# Axel.net
KiCad netlist of a schematic drawn in Altium Designer
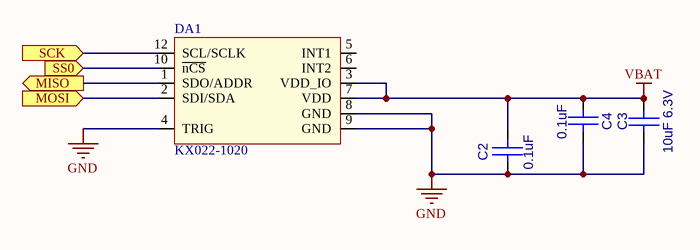
[diagram p0: Axel.SchDoc]

(export (version "E")
  (design (tool "Eeschema 10.0.6"))
  (components
    (comp (ref "C2")
      (value "0.1uF")
      (footprint "CC0603")
      (description "CC0603")
      (libsource (lib "gprs_modem_2") (part "CC0603"))
    )
    (comp (ref "C3")
      (value "10uF 6.3V")
      (footprint "CC0805")
      (description "CC0805")
      (libsource (lib "gprs_modem_2") (part "CC0805"))
    )
    (comp (ref "C4")
      (value "0.1uF")
      (footprint "CC0603")
      (description "CC0603")
      (libsource (lib "gprs_modem_2") (part "CC0603"))
    )
    (comp (ref "DA1")
      (value "KX022-1020")
      (footprint "LGA-12")
      (libsource (lib "gprs_modem_2") (part "KX022-1020"))
    )
  )
  (nets
    (net (code "1") (name "/MISO") (class "Default")
      (node (ref "DA1") (pin "1") (pinfunction "SDO/ADDR_1") (pintype "passive"))
    )
    (net (code "2") (name "/MOSI") (class "Default")
      (node (ref "DA1") (pin "2") (pinfunction "SDI/SDA_2") (pintype "passive"))
    )
    (net (code "3") (name "/SCK") (class "Default")
      (node (ref "DA1") (pin "12") (pinfunction "SCL/SCLK_12") (pintype "passive"))
    )
    (net (code "4") (name "/SS0") (class "Default")
      (node (ref "DA1") (pin "10") (pinfunction "~{nCS}_10") (pintype "passive"))
    )
    (net (code "5") (name "GND") (class "Default")
      (node (ref "C2") (pin "2") (pinfunction "B_2") (pintype "passive"))
      (node (ref "C3") (pin "1") (pinfunction "A_1") (pintype "passive"))
      (node (ref "C4") (pin "2") (pinfunction "B_2") (pintype "passive"))
      (node (ref "DA1") (pin "4") (pinfunction "TRIG_4") (pintype "passive"))
      (node (ref "DA1") (pin "8") (pinfunction "GND_8") (pintype "passive"))
      (node (ref "DA1") (pin "9") (pinfunction "GND_9") (pintype "passive"))
    )
    (net (code "6") (name "VBAT") (class "Default")
      (node (ref "C2") (pin "1") (pinfunction "A_1") (pintype "passive"))
      (node (ref "C3") (pin "2") (pinfunction "B_2") (pintype "passive"))
      (node (ref "C4") (pin "1") (pinfunction "A_1") (pintype "passive"))
      (node (ref "DA1") (pin "3") (pinfunction "VDD_IO_3") (pintype "passive"))
      (node (ref "DA1") (pin "7") (pinfunction "VDD_7") (pintype "passive"))
    )
    (net (code "7") (name "unconnected-(DA1-INT1-Pad5)") (class "Default")
      (node (ref "DA1") (pin "5") (pinfunction "INT1_5") (pintype "passive"))
    )
    (net (code "8") (name "unconnected-(DA1-INT2-Pad6)") (class "Default")
      (node (ref "DA1") (pin "6") (pinfunction "INT2_6") (pintype "passive"))
    )
  )
)
